# usb-hub.net
KiCad netlist of a schematic drawn in EasyEDA Pro
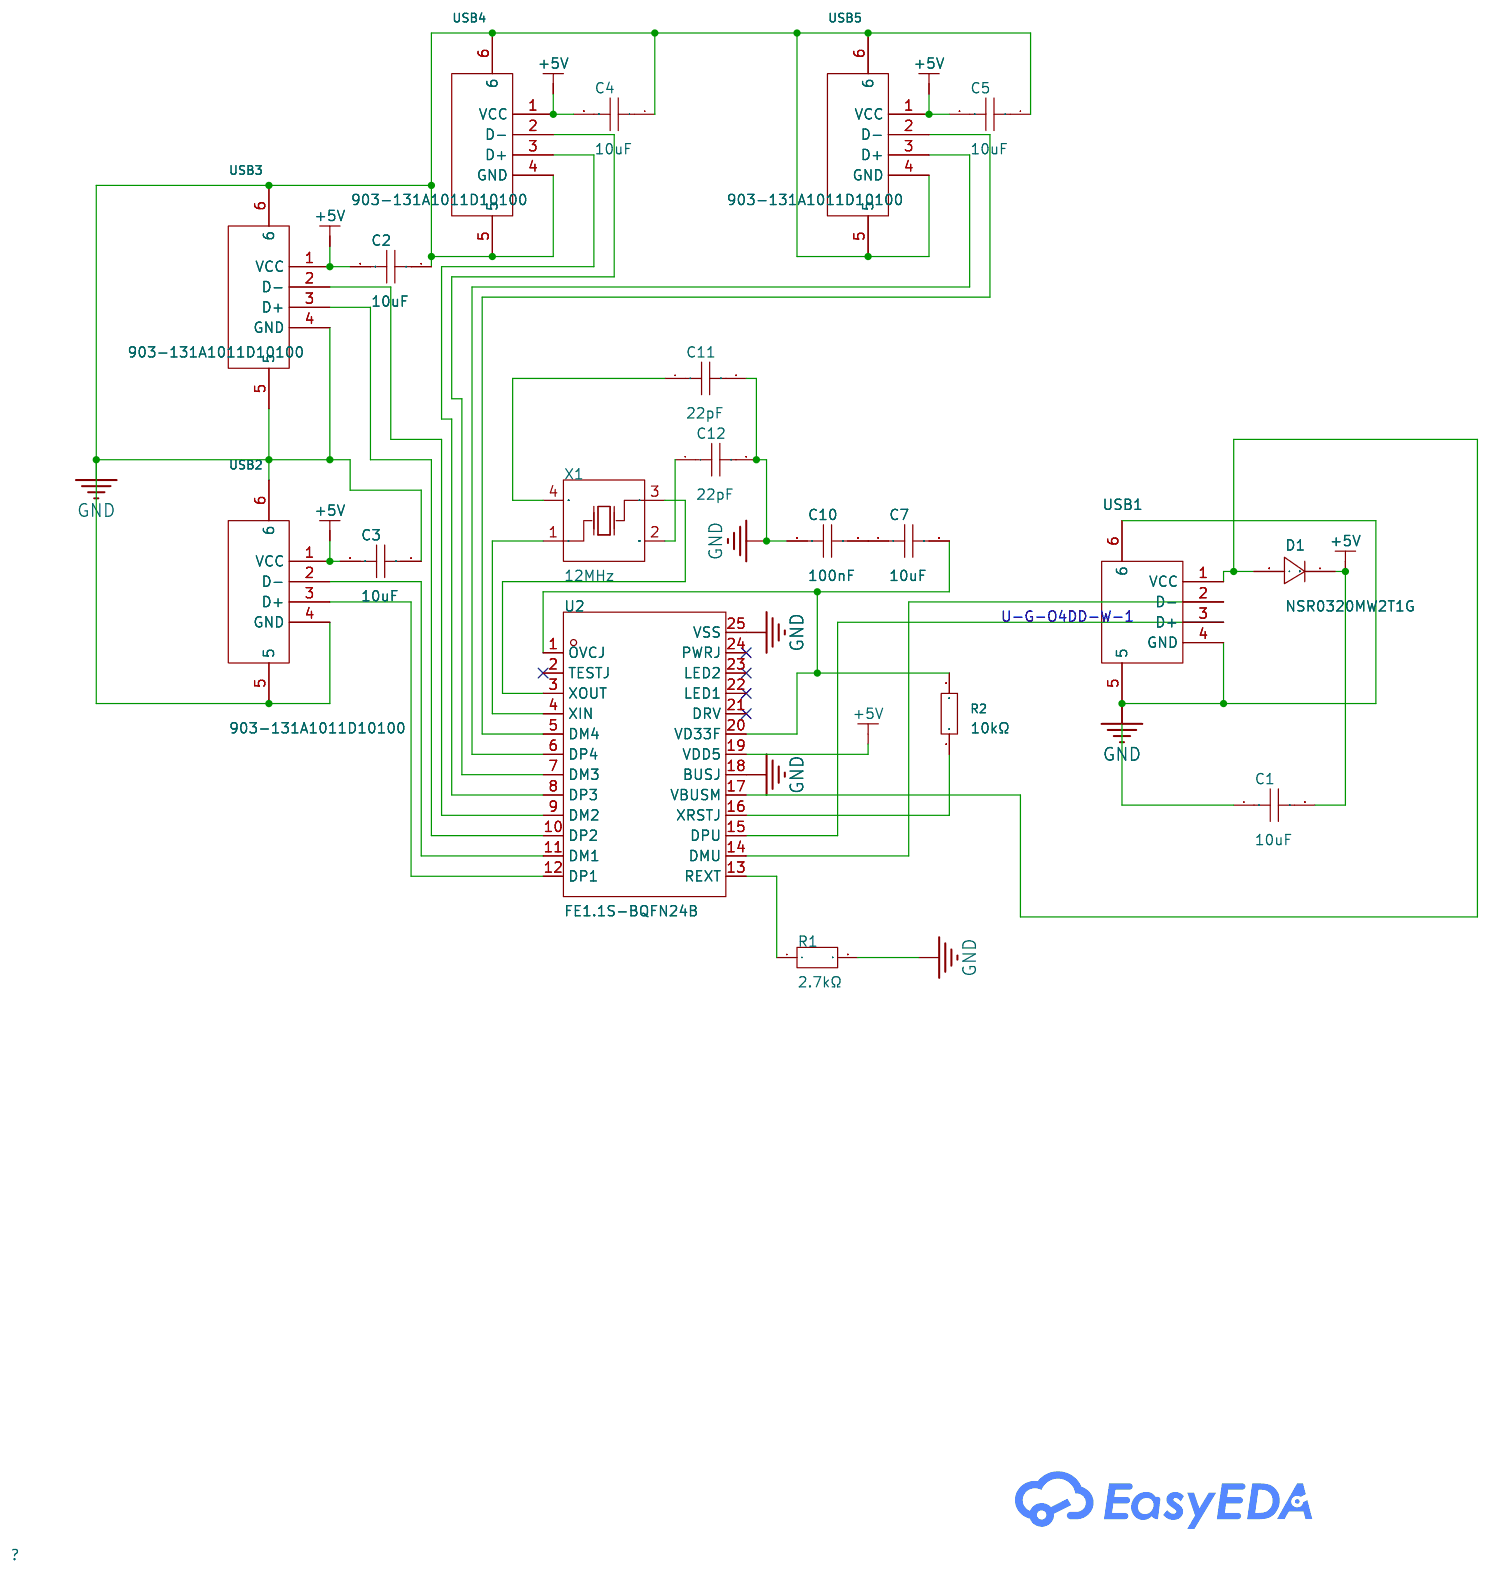
[diagram p0: schematic sheet]

(export (version "E")
  (design (tool "Eeschema 10.0.6"))
  (components
    (comp (ref "C1")
      (value "10uF")
      (footprint "easyedapro:C0603")
      (description "Capacitance:10uF Tolerance:±10% Tolerance:±10% Voltage Rating:10V Temperature Coefficient:X5R")
      (fields
        (field (name "Manufacturer Part") "CL10A106KP8NNNC")
        (field (name "Manufacturer") "SAMSUNG(三星)")
      )
      (libsource (lib "easyedapro") (part "CL10A106KP8NNNC"))
    )
    (comp (ref "C2")
      (value "10uF")
      (footprint "easyedapro:C0603")
      (description "Capacitance:10uF Tolerance:±10% Tolerance:±10% Voltage Rating:10V Temperature Coefficient:X5R")
      (fields
        (field (name "Manufacturer Part") "CL10A106KP8NNNC")
        (field (name "Manufacturer") "SAMSUNG(三星)")
      )
      (libsource (lib "easyedapro") (part "CL10A106KP8NNNC"))
    )
    (comp (ref "C3")
      (value "10uF")
      (footprint "easyedapro:C0603")
      (description "Capacitance:10uF Tolerance:±10% Tolerance:±10% Voltage Rating:10V Temperature Coefficient:X5R")
      (fields
        (field (name "Manufacturer Part") "CL10A106KP8NNNC")
        (field (name "Manufacturer") "SAMSUNG(三星)")
      )
      (libsource (lib "easyedapro") (part "CL10A106KP8NNNC"))
    )
    (comp (ref "C4")
      (value "10uF")
      (footprint "easyedapro:C0603")
      (description "Capacitance:10uF Tolerance:±10% Tolerance:±10% Voltage Rating:10V Temperature Coefficient:X5R")
      (fields
        (field (name "Manufacturer Part") "CL10A106KP8NNNC")
        (field (name "Manufacturer") "SAMSUNG(三星)")
      )
      (libsource (lib "easyedapro") (part "CL10A106KP8NNNC"))
    )
    (comp (ref "C5")
      (value "10uF")
      (footprint "easyedapro:C0603")
      (description "Capacitance:10uF Tolerance:±10% Tolerance:±10% Voltage Rating:10V Temperature Coefficient:X5R")
      (fields
        (field (name "Manufacturer Part") "CL10A106KP8NNNC")
        (field (name "Manufacturer") "SAMSUNG(三星)")
      )
      (libsource (lib "easyedapro") (part "CL10A106KP8NNNC"))
    )
    (comp (ref "C7")
      (value "10uF")
      (footprint "easyedapro:C0603")
      (description "Capacitance:10uF Tolerance:±10% Tolerance:±10% Voltage Rating:10V Temperature Coefficient:X5R")
      (fields
        (field (name "Manufacturer Part") "CL10A106KP8NNNC")
        (field (name "Manufacturer") "SAMSUNG(三星)")
      )
      (libsource (lib "easyedapro") (part "CL10A106KP8NNNC"))
    )
    (comp (ref "C10")
      (value "100nF")
      (footprint "easyedapro:C0402")
      (description "Capacitance:100nF Tolerance:±10% Tolerance:±10% Voltage Rating:16V Temperature Coefficient:X7R")
      (fields
        (field (name "Manufacturer Part") "CL05B104KO5NNNC")
        (field (name "Manufacturer") "SAMSUNG(三星)")
      )
      (libsource (lib "easyedapro") (part "CL05B104KO5NNNC"))
    )
    (comp (ref "C11")
      (value "22pF")
      (footprint "easyedapro:CAP-TH_L4.8-W3.2-P5.08-D0.5")
      (description "Capacitance:22pF Tolerance:±5% Tolerance:±5% Voltage Rating:50V Temperature Coefficient:-")
      (fields
        (field (name "Manufacturer Part") "CC4-0805-CG-50V-22pF-J")
        (field (name "Manufacturer") "TORCH(火炬)")
      )
      (libsource (lib "easyedapro") (part "CC4-0805-CG -50V-22pF-J"))
    )
    (comp (ref "C12")
      (value "22pF")
      (footprint "easyedapro:CAP-TH_L4.8-W3.2-P5.08-D0.5")
      (description "Capacitance:22pF Tolerance:±5% Tolerance:±5% Voltage Rating:50V Temperature Coefficient:-")
      (fields
        (field (name "Manufacturer Part") "CC4-0805-CG-50V-22pF-J")
        (field (name "Manufacturer") "TORCH(火炬)")
      )
      (libsource (lib "easyedapro") (part "CC4-0805-CG -50V-22pF-J"))
    )
    (comp (ref "D1")
      (value "NSR0320MW2T1G")
      (footprint "easyedapro:SOD-323_L1.8-W1.3-LS2.5-RD")
      (fields (field (name "Manufacturer") "onsemi(安森美)"))
      (libsource (lib "easyedapro") (part "NSR0320MW2T1G"))
    )
    (comp (ref "R1")
      (value "2.7kΩ")
      (footprint "easyedapro:RES-TH_BD1.8-L3.2-P7.20-D0.4")
      (fields (field (name "Manufacturer Part") "MF1/8W-2.7KΩ±1%T52") (field (name "Manufacturer") "华星机电"))
      (libsource (lib "easyedapro") (part "MF1/8W-2.7KΩ±1%T52"))
    )
    (comp (ref "R2")
      (value "10kΩ")
      (footprint "easyedapro:R1206")
      (fields
        (field (name "Manufacturer Part") "1206W4F1002T5E")
        (field (name "Manufacturer") "UNI-ROYAL(厚声)")
      )
      (libsource (lib "easyedapro") (part "1206W4F1002T5E"))
    )
    (comp (ref "U2")
      (value "FE1.1S-BQFN24B")
      (footprint "easyedapro:WQFN-24_L4.0-W4.0-P0.50-TL-EP2.7")
      (fields (field (name "Manufacturer") "TERMINUS"))
      (libsource (lib "easyedapro") (part "FE1.1S-BQFN24B"))
    )
    (comp (ref "USB1")
      (value "U-G-O4DD-W-1")
      (footprint "easyedapro:USB-A-TH_U-G-04WD-W-01")
      (fields (field (name "Manufacturer") "韩国韩荣"))
      (libsource (lib "easyedapro") (part "U-G-04DD-W-01"))
    )
    (comp (ref "USB2")
      (value "903-131A1011D10100")
      (footprint "easyedapro:USB-A-TH_C46407")
      (fields (field (name "Manufacturer") "精拓金"))
      (libsource (lib "easyedapro") (part "USB-AF-90-14.4X13.6-H7.0-DIP"))
    )
    (comp (ref "USB3")
      (value "903-131A1011D10100")
      (footprint "easyedapro:USB-A-TH_C46407")
      (fields (field (name "Manufacturer") "精拓金"))
      (libsource (lib "easyedapro") (part "USB-AF-90-14.4X13.6-H7.0-DIP"))
    )
    (comp (ref "USB4")
      (value "903-131A1011D10100")
      (footprint "easyedapro:USB-A-TH_C46407")
      (fields (field (name "Manufacturer") "精拓金"))
      (libsource (lib "easyedapro") (part "USB-AF-90-14.4X13.6-H7.0-DIP"))
    )
    (comp (ref "USB5")
      (value "903-131A1011D10100")
      (footprint "easyedapro:USB-A-TH_C46407")
      (fields (field (name "Manufacturer") "精拓金"))
      (libsource (lib "easyedapro") (part "USB-AF-90-14.4X13.6-H7.0-DIP"))
    )
    (comp (ref "X1")
      (value "12MHz")
      (footprint "easyedapro:OSC-SMD_4P-L7.0-W5.0-BL")
      (fields
        (field (name "Manufacturer Part") "OCETDLJANF-12MHZ")
        (field (name "Manufacturer") "TAITIEN(泰艺电子)")
      )
      (libsource (lib "easyedapro") (part "OCETDLJANF-12MHZ"))
    )
  )
  (nets
    (net (code "1") (name "+5V") (class "Default")
      (node (ref "C1") (pin "2") (pinfunction "2_2") (pintype "unspecified"))
      (node (ref "C2") (pin "2") (pinfunction "2_2") (pintype "unspecified"))
      (node (ref "C3") (pin "2") (pinfunction "2_2") (pintype "unspecified"))
      (node (ref "C4") (pin "2") (pinfunction "2_2") (pintype "unspecified"))
      (node (ref "C5") (pin "2") (pinfunction "2_2") (pintype "unspecified"))
      (node (ref "D1") (pin "1") (pinfunction "C_1") (pintype "unspecified"))
      (node (ref "U2") (pin "19") (pinfunction "VDD5_19") (pintype "unspecified"))
      (node (ref "USB2") (pin "1") (pinfunction "VCC_1") (pintype "input"))
      (node (ref "USB3") (pin "1") (pinfunction "VCC_1") (pintype "input"))
      (node (ref "USB4") (pin "1") (pinfunction "VCC_1") (pintype "input"))
      (node (ref "USB5") (pin "1") (pinfunction "VCC_1") (pintype "input"))
    )
    (net (code "2") (name "GND") (class "Default")
      (node (ref "C1") (pin "1") (pinfunction "1_1") (pintype "unspecified"))
      (node (ref "C10") (pin "1") (pinfunction "1_1") (pintype "unspecified"))
      (node (ref "C11") (pin "2") (pinfunction "2_2") (pintype "unspecified"))
      (node (ref "C12") (pin "2") (pinfunction "2_2") (pintype "unspecified"))
      (node (ref "C2") (pin "1") (pinfunction "1_1") (pintype "unspecified"))
      (node (ref "C3") (pin "1") (pinfunction "1_1") (pintype "unspecified"))
      (node (ref "C4") (pin "1") (pinfunction "1_1") (pintype "unspecified"))
      (node (ref "C5") (pin "1") (pinfunction "1_1") (pintype "unspecified"))
      (node (ref "R1") (pin "2") (pinfunction "2_2") (pintype "unspecified"))
      (node (ref "U2") (pin "18") (pinfunction "BUSJ_18") (pintype "unspecified"))
      (node (ref "U2") (pin "25") (pinfunction "VSS_25") (pintype "unspecified"))
      (node (ref "USB1") (pin "4") (pinfunction "GND_4") (pintype "unspecified"))
      (node (ref "USB1") (pin "5") (pinfunction "5_5") (pintype "unspecified"))
      (node (ref "USB1") (pin "6") (pinfunction "6_6") (pintype "unspecified"))
      (node (ref "USB2") (pin "4") (pinfunction "GND_4") (pintype "input"))
      (node (ref "USB2") (pin "5") (pinfunction "5_5") (pintype "input"))
      (node (ref "USB2") (pin "6") (pinfunction "6_6") (pintype "input"))
      (node (ref "USB3") (pin "4") (pinfunction "GND_4") (pintype "input"))
      (node (ref "USB3") (pin "5") (pinfunction "5_5") (pintype "input"))
      (node (ref "USB3") (pin "6") (pinfunction "6_6") (pintype "input"))
      (node (ref "USB4") (pin "4") (pinfunction "GND_4") (pintype "input"))
      (node (ref "USB4") (pin "5") (pinfunction "5_5") (pintype "input"))
      (node (ref "USB4") (pin "6") (pinfunction "6_6") (pintype "input"))
      (node (ref "USB5") (pin "4") (pinfunction "GND_4") (pintype "input"))
      (node (ref "USB5") (pin "5") (pinfunction "5_5") (pintype "input"))
      (node (ref "USB5") (pin "6") (pinfunction "6_6") (pintype "input"))
    )
    (net (code "3") (name "Net-(C10-Pad2)") (class "Default")
      (node (ref "C10") (pin "2") (pinfunction "2_2") (pintype "unspecified"))
      (node (ref "C7") (pin "1") (pinfunction "1_1") (pintype "unspecified"))
    )
    (net (code "4") (name "Net-(D1-A)") (class "Default")
      (node (ref "D1") (pin "2") (pinfunction "A_2") (pintype "unspecified"))
      (node (ref "U2") (pin "17") (pinfunction "VBUSM_17") (pintype "unspecified"))
      (node (ref "USB1") (pin "1") (pinfunction "VCC_1") (pintype "unspecified"))
    )
    (net (code "5") (name "Net-(U2-DM1)") (class "Default")
      (node (ref "U2") (pin "11") (pinfunction "DM1_11") (pintype "unspecified"))
      (node (ref "USB2") (pin "2") (pinfunction "D-_2") (pintype "input"))
    )
    (net (code "6") (name "Net-(U2-DM2)") (class "Default")
      (node (ref "U2") (pin "9") (pinfunction "DM2_9") (pintype "unspecified"))
      (node (ref "USB3") (pin "2") (pinfunction "D-_2") (pintype "input"))
    )
    (net (code "7") (name "Net-(U2-DM3)") (class "Default")
      (node (ref "U2") (pin "7") (pinfunction "DM3_7") (pintype "unspecified"))
      (node (ref "USB4") (pin "2") (pinfunction "D-_2") (pintype "input"))
    )
    (net (code "8") (name "Net-(U2-DM4)") (class "Default")
      (node (ref "U2") (pin "5") (pinfunction "DM4_5") (pintype "unspecified"))
      (node (ref "USB5") (pin "2") (pinfunction "D-_2") (pintype "input"))
    )
    (net (code "9") (name "Net-(U2-DMU)") (class "Default")
      (node (ref "U2") (pin "14") (pinfunction "DMU_14") (pintype "unspecified"))
      (node (ref "USB1") (pin "2") (pinfunction "D-_2") (pintype "unspecified"))
    )
    (net (code "10") (name "Net-(U2-DP1)") (class "Default")
      (node (ref "U2") (pin "12") (pinfunction "DP1_12") (pintype "unspecified"))
      (node (ref "USB2") (pin "3") (pinfunction "D+_3") (pintype "input"))
    )
    (net (code "11") (name "Net-(U2-DP2)") (class "Default")
      (node (ref "U2") (pin "10") (pinfunction "DP2_10") (pintype "unspecified"))
      (node (ref "USB3") (pin "3") (pinfunction "D+_3") (pintype "input"))
    )
    (net (code "12") (name "Net-(U2-DP3)") (class "Default")
      (node (ref "U2") (pin "8") (pinfunction "DP3_8") (pintype "unspecified"))
      (node (ref "USB4") (pin "3") (pinfunction "D+_3") (pintype "input"))
    )
    (net (code "13") (name "Net-(U2-DP4)") (class "Default")
      (node (ref "U2") (pin "6") (pinfunction "DP4_6") (pintype "unspecified"))
      (node (ref "USB5") (pin "3") (pinfunction "D+_3") (pintype "input"))
    )
    (net (code "14") (name "Net-(U2-DPU)") (class "Default")
      (node (ref "U2") (pin "15") (pinfunction "DPU_15") (pintype "unspecified"))
      (node (ref "USB1") (pin "3") (pinfunction "D+_3") (pintype "unspecified"))
    )
    (net (code "15") (name "Net-(U2-OVCJ)") (class "Default")
      (node (ref "C7") (pin "2") (pinfunction "2_2") (pintype "unspecified"))
      (node (ref "R2") (pin "2") (pinfunction "2_2") (pintype "input"))
      (node (ref "U2") (pin "1") (pinfunction "OVCJ_1") (pintype "unspecified"))
      (node (ref "U2") (pin "20") (pinfunction "VD33F_20") (pintype "unspecified"))
    )
    (net (code "16") (name "Net-(U2-REXT)") (class "Default")
      (node (ref "R1") (pin "1") (pinfunction "1_1") (pintype "unspecified"))
      (node (ref "U2") (pin "13") (pinfunction "REXT_13") (pintype "unspecified"))
    )
    (net (code "17") (name "Net-(U2-XIN)") (class "Default")
      (node (ref "U2") (pin "4") (pinfunction "XIN_4") (pintype "unspecified"))
      (node (ref "X1") (pin "1") (pinfunction "tri_1") (pintype "unspecified"))
    )
    (net (code "18") (name "Net-(U2-XOUT)") (class "Default")
      (node (ref "U2") (pin "3") (pinfunction "XOUT_3") (pintype "unspecified"))
      (node (ref "X1") (pin "3") (pinfunction "out_3") (pintype "unspecified"))
    )
    (net (code "19") (name "Net-(U2-XRSTJ)") (class "Default")
      (node (ref "R2") (pin "1") (pinfunction "1_1") (pintype "input"))
      (node (ref "U2") (pin "16") (pinfunction "XRSTJ_16") (pintype "unspecified"))
    )
    (net (code "20") (name "Net-(X1-GND)") (class "Default")
      (node (ref "C12") (pin "1") (pinfunction "1_1") (pintype "unspecified"))
      (node (ref "X1") (pin "2") (pinfunction "GND_2") (pintype "unspecified"))
    )
    (net (code "21") (name "Net-(X1-vdd)") (class "Default")
      (node (ref "C11") (pin "1") (pinfunction "1_1") (pintype "unspecified"))
      (node (ref "X1") (pin "4") (pinfunction "vdd_4") (pintype "unspecified"))
    )
    (net (code "22") (name "unconnected-(U2-DRV-Pad21)") (class "Default")
      (node (ref "U2") (pin "21") (pinfunction "DRV_21") (pintype "unspecified+no_connect"))
    )
    (net (code "23") (name "unconnected-(U2-LED1-Pad22)") (class "Default")
      (node (ref "U2") (pin "22") (pinfunction "LED1_22") (pintype "unspecified+no_connect"))
    )
    (net (code "24") (name "unconnected-(U2-LED2-Pad23)") (class "Default")
      (node (ref "U2") (pin "23") (pinfunction "LED2_23") (pintype "unspecified+no_connect"))
    )
    (net (code "25") (name "unconnected-(U2-PWRJ-Pad24)") (class "Default")
      (node (ref "U2") (pin "24") (pinfunction "PWRJ_24") (pintype "unspecified+no_connect"))
    )
    (net (code "26") (name "unconnected-(U2-TESTJ-Pad2)") (class "Default")
      (node (ref "U2") (pin "2") (pinfunction "TESTJ_2") (pintype "unspecified+no_connect"))
    )
  )
)
